# IMD_Filtering.net
KiCad netlist of a schematic drawn in Altium Designer
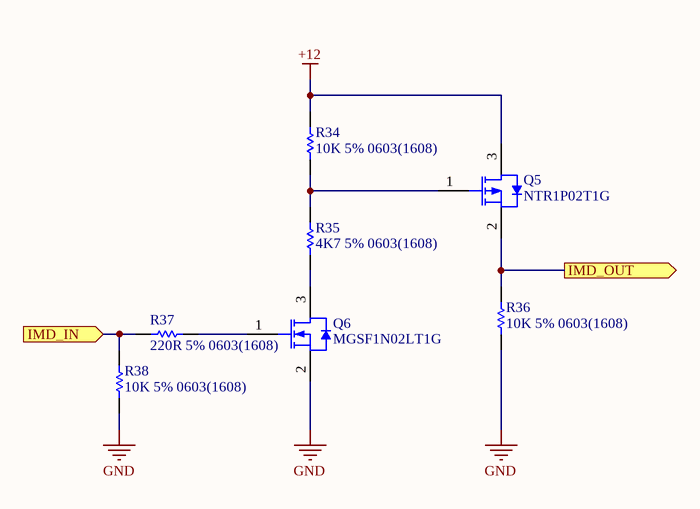
[diagram p0: IMD_Filtering.SchDoc]

(export (version "E")
  (design (tool "Eeschema 10.0.6"))
  (components
    (comp (ref "Q5")
      (value "NTR1P02T1G")
      (footprint "ONSC-SOT-23-3-318-08_V")
      (description "Power MOSFET, -20 V, -1 A, P-Channel, 3-Pin SOT-23, Pb-Free, Tape and Reel")
      (fields (field (name "MANUFACTURER") "On Semiconductor"))
      (libsource (lib "Altium Content Vault") (part "ONSC-PMOS-G1S2D3-3_D"))
    )
    (comp (ref "Q6")
      (value "MGSF1N02LT1G")
      (footprint "ONSC-SOT-23-3-318-08_V")
      (description "Power MOSFET, 750 mA, 20 V, N-Channel, 3-Pin SOT-23, Pb-Free, Tape and Reel")
      (fields (field (name "MANUFACTURER") "On Semiconductor"))
      (libsource (lib "Altium Content Vault") (part "ONSC-NMOS-G1S2D3-3"))
    )
    (comp (ref "R34")
      (value "10K 5% 0603(1608)")
      (footprint "RESC0603(1608)_N")
      (description "10K 0.1W 5% 0603 (1608 Metric)  SMD")
      (fields (field (name "TOLERANCE") "5 %") (field (name "POWER") "0.1 W"))
      (libsource (lib "Altium Content Vault") (part "RES"))
    )
    (comp (ref "R35")
      (value "4K7 5% 0603(1608)")
      (footprint "RESC0603(1608)_N")
      (description "4K7 0.1W 5% 0603 (1608 Metric)  SMD")
      (fields (field (name "TOLERANCE") "5 %") (field (name "POWER") "0.1 W"))
      (libsource (lib "Altium Content Vault") (part "RES"))
    )
    (comp (ref "R36")
      (value "10K 5% 0603(1608)")
      (footprint "RESC0603(1608)_N")
      (description "10K 0.1W 5% 0603 (1608 Metric)  SMD")
      (fields (field (name "TOLERANCE") "5 %") (field (name "POWER") "0.1 W"))
      (libsource (lib "Altium Content Vault") (part "RES"))
    )
    (comp (ref "R37")
      (value "220R 5% 0603(1608)")
      (footprint "RESC0603(1608)_M")
      (description "220R 0.1W 5% 0603 (1608 Metric)  SMD")
      (fields (field (name "POWER") "0.1 W") (field (name "TOLERANCE") "5 %"))
      (libsource (lib "Altium Content Vault") (part "RES"))
    )
    (comp (ref "R38")
      (value "10K 5% 0603(1608)")
      (footprint "RESC0603(1608)_N")
      (description "10K 0.1W 5% 0603 (1608 Metric)  SMD")
      (fields (field (name "TOLERANCE") "5 %") (field (name "POWER") "0.1 W"))
      (libsource (lib "Altium Content Vault") (part "RES"))
    )
  )
  (nets
    (net (code "1") (name "+12") (class "Default")
      (node (ref "Q5") (pin "3") (pinfunction "D_3") (pintype "passive"))
      (node (ref "R34") (pin "2") (pinfunction "2_2") (pintype "passive"))
    )
    (net (code "2") (name "/IMD_IN") (class "Default")
      (node (ref "R37") (pin "1") (pinfunction "1_1") (pintype "passive"))
      (node (ref "R38") (pin "2") (pinfunction "2_2") (pintype "passive"))
    )
    (net (code "3") (name "/IMD_OUT") (class "Default")
      (node (ref "Q5") (pin "2") (pinfunction "S_2") (pintype "passive"))
      (node (ref "R36") (pin "2") (pinfunction "2_2") (pintype "passive"))
    )
    (net (code "4") (name "GND") (class "Default")
      (node (ref "Q6") (pin "2") (pinfunction "S_2") (pintype "passive"))
      (node (ref "R36") (pin "1") (pinfunction "1_1") (pintype "passive"))
      (node (ref "R38") (pin "1") (pinfunction "1_1") (pintype "passive"))
    )
    (net (code "5") (name "Net-(Q5-G)") (class "Default")
      (node (ref "Q5") (pin "1") (pinfunction "G_1") (pintype "passive"))
      (node (ref "R34") (pin "1") (pinfunction "1_1") (pintype "passive"))
      (node (ref "R35") (pin "2") (pinfunction "2_2") (pintype "passive"))
    )
    (net (code "6") (name "Net-(Q6-D)") (class "Default")
      (node (ref "Q6") (pin "3") (pinfunction "D_3") (pintype "passive"))
      (node (ref "R35") (pin "1") (pinfunction "1_1") (pintype "passive"))
    )
    (net (code "7") (name "Net-(Q6-G)") (class "Default")
      (node (ref "Q6") (pin "1") (pinfunction "G_1") (pintype "passive"))
      (node (ref "R37") (pin "2") (pinfunction "2_2") (pintype "passive"))
    )
  )
)
